# MCU_IO.net
KiCad netlist of a schematic drawn in Altium Designer
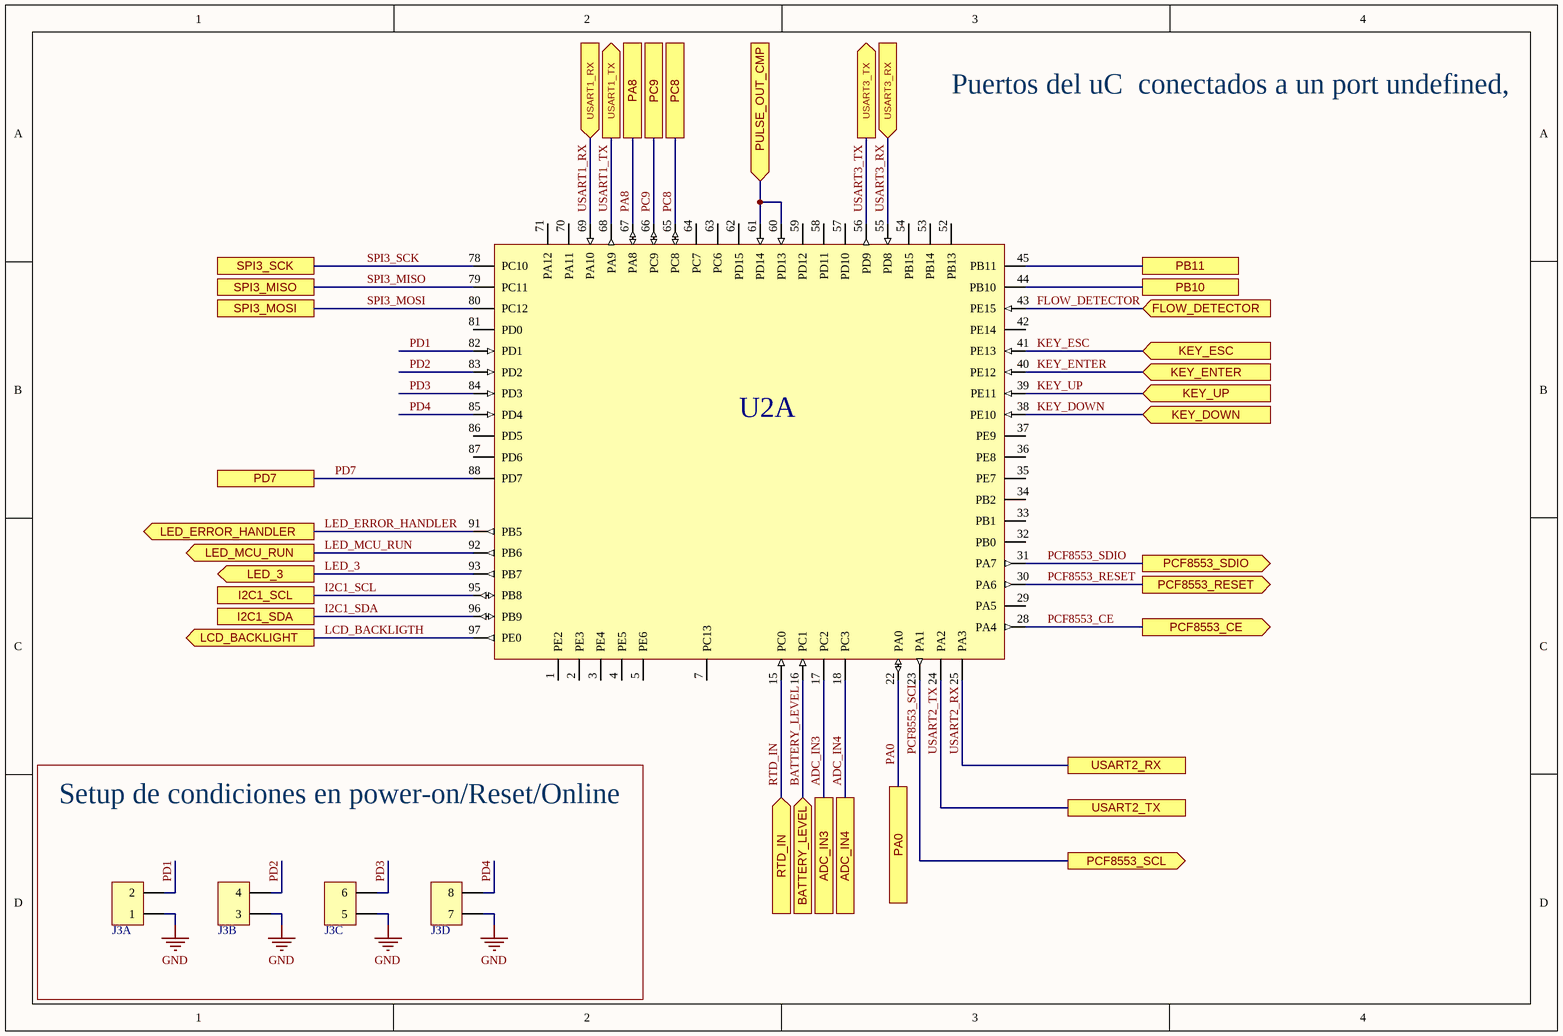
[diagram p0: MCU_IO.SchDoc]

(export (version "E")
  (design (tool "Eeschema 10.0.6"))
  (components
    (comp (ref "J3")
      (value "B-2100S08P-B110-JUMPER")
      (footprint "HEADER PIN 2X4")
      (description "2 x 4 - true hole  2.54mm")
      (fields
        (field (name "MANUFACTURER") "Ckmtw")
        (field (name "MANUFACTURER PART NUMBER") "B-2100S08P-B110")
      )
      (libsource (lib "header_pin") (part "B-2100S08P-B110-JUMPER"))
    )
    (comp (ref "U2")
      (value "STM32U575VI_1")
      (footprint "STM32U575VI")
      (fields (field (name "MANUFACTURER") "ST") (field (name "MANUFACTURER PART NUMBER") "STM32U575VIT6Q"))
      (libsource (lib "Microcontroladores") (part "STM32U575VI_1"))
    )
  )
  (nets
    (net (code "1") (name "/ADC_IN3") (class "Default")
      (node (ref "U2") (pin "17") (pinfunction "PC2_17") (pintype "tri_state"))
    )
    (net (code "2") (name "/ADC_IN4") (class "Default")
      (node (ref "U2") (pin "18") (pinfunction "PC3_18") (pintype "tri_state"))
    )
    (net (code "3") (name "/BATTERY_LEVEL") (class "Default")
      (node (ref "U2") (pin "16") (pinfunction "PC1_16") (pintype "input"))
    )
    (net (code "4") (name "/FLOW_DETECTOR") (class "Default")
      (node (ref "U2") (pin "43") (pinfunction "PE15_43") (pintype "input"))
    )
    (net (code "5") (name "/I2C1_SCL") (class "Default")
      (node (ref "U2") (pin "95") (pinfunction "PB8_95") (pintype "bidirectional"))
    )
    (net (code "6") (name "/I2C1_SDA") (class "Default")
      (node (ref "U2") (pin "96") (pinfunction "PB9_96") (pintype "bidirectional"))
    )
    (net (code "7") (name "/KEY_DOWN") (class "Default")
      (node (ref "U2") (pin "38") (pinfunction "PE10_38") (pintype "input"))
    )
    (net (code "8") (name "/KEY_ENTER") (class "Default")
      (node (ref "U2") (pin "40") (pinfunction "PE12_40") (pintype "input"))
    )
    (net (code "9") (name "/KEY_ESC") (class "Default")
      (node (ref "U2") (pin "41") (pinfunction "PE13_41") (pintype "input"))
    )
    (net (code "10") (name "/KEY_UP") (class "Default")
      (node (ref "U2") (pin "39") (pinfunction "PE11_39") (pintype "input"))
    )
    (net (code "11") (name "/LCD_BACKLIGTH") (class "Default")
      (node (ref "U2") (pin "97") (pinfunction "PE0_97") (pintype "output"))
    )
    (net (code "12") (name "/LED_3") (class "Default")
      (node (ref "U2") (pin "93") (pinfunction "PB7_93") (pintype "output"))
    )
    (net (code "13") (name "/LED_ERROR_HANDLER") (class "Default")
      (node (ref "U2") (pin "91") (pinfunction "PB5_91") (pintype "output"))
    )
    (net (code "14") (name "/LED_MCU_RUN") (class "Default")
      (node (ref "U2") (pin "92") (pinfunction "PB6_92") (pintype "output"))
    )
    (net (code "15") (name "/PA0") (class "Default")
      (node (ref "U2") (pin "22") (pinfunction "PA0_22") (pintype "bidirectional"))
    )
    (net (code "16") (name "/PA8") (class "Default")
      (node (ref "U2") (pin "67") (pinfunction "PA8_67") (pintype "bidirectional"))
    )
    (net (code "17") (name "/PB10") (class "Default")
      (node (ref "U2") (pin "44") (pinfunction "PB10_44") (pintype "tri_state"))
    )
    (net (code "18") (name "/PB11") (class "Default")
      (node (ref "U2") (pin "45") (pinfunction "PB11_45") (pintype "tri_state"))
    )
    (net (code "19") (name "/PC8") (class "Default")
      (node (ref "U2") (pin "65") (pinfunction "PC8_65") (pintype "bidirectional"))
    )
    (net (code "20") (name "/PC9") (class "Default")
      (node (ref "U2") (pin "66") (pinfunction "PC9_66") (pintype "bidirectional"))
    )
    (net (code "21") (name "/PCF8553_CE") (class "Default")
      (node (ref "U2") (pin "28") (pinfunction "PA4_28") (pintype "output"))
    )
    (net (code "22") (name "/PCF8553_RESET") (class "Default")
      (node (ref "U2") (pin "30") (pinfunction "PA6_30") (pintype "output"))
    )
    (net (code "23") (name "/PCF8553_SCL") (class "Default")
      (node (ref "U2") (pin "23") (pinfunction "PA1_23") (pintype "output"))
    )
    (net (code "24") (name "/PCF8553_SDIO") (class "Default")
      (node (ref "U2") (pin "31") (pinfunction "PA7_31") (pintype "output"))
    )
    (net (code "25") (name "/PD1") (class "Default")
      (node (ref "J3") (pin "2") (pinfunction "2_2") (pintype "passive"))
      (node (ref "U2") (pin "82") (pinfunction "PD1_82") (pintype "input"))
    )
    (net (code "26") (name "/PD2") (class "Default")
      (node (ref "J3") (pin "4") (pinfunction "4_4") (pintype "passive"))
      (node (ref "U2") (pin "83") (pinfunction "PD2_83") (pintype "input"))
    )
    (net (code "27") (name "/PD3") (class "Default")
      (node (ref "J3") (pin "6") (pinfunction "6_6") (pintype "passive"))
      (node (ref "U2") (pin "84") (pinfunction "PD3_84") (pintype "input"))
    )
    (net (code "28") (name "/PD4") (class "Default")
      (node (ref "J3") (pin "8") (pinfunction "8_8") (pintype "passive"))
      (node (ref "U2") (pin "85") (pinfunction "PD4_85") (pintype "input"))
    )
    (net (code "29") (name "/PD7") (class "Default")
      (node (ref "U2") (pin "88") (pinfunction "PD7_88") (pintype "passive"))
    )
    (net (code "30") (name "/PULSE_OUT_CMP") (class "Default")
      (node (ref "U2") (pin "60") (pinfunction "PD13_60") (pintype "input"))
      (node (ref "U2") (pin "61") (pinfunction "PD14_61") (pintype "input"))
    )
    (net (code "31") (name "/RTD_IN") (class "Default")
      (node (ref "U2") (pin "15") (pinfunction "PC0_15") (pintype "input"))
    )
    (net (code "32") (name "/SPI3_MISO") (class "Default")
      (node (ref "U2") (pin "79") (pinfunction "PC11_79") (pintype "tri_state"))
    )
    (net (code "33") (name "/SPI3_MOSI") (class "Default")
      (node (ref "U2") (pin "80") (pinfunction "PC12_80") (pintype "tri_state"))
    )
    (net (code "34") (name "/SPI3_SCK") (class "Default")
      (node (ref "U2") (pin "78") (pinfunction "PC10_78") (pintype "tri_state"))
    )
    (net (code "35") (name "/USART1_RX") (class "Default")
      (node (ref "U2") (pin "69") (pinfunction "PA10_69") (pintype "input"))
    )
    (net (code "36") (name "/USART1_TX") (class "Default")
      (node (ref "U2") (pin "68") (pinfunction "PA9_68") (pintype "output"))
    )
    (net (code "37") (name "/USART2_RX") (class "Default")
      (node (ref "U2") (pin "25") (pinfunction "PA3_25") (pintype "tri_state"))
    )
    (net (code "38") (name "/USART2_TX") (class "Default")
      (node (ref "U2") (pin "24") (pinfunction "PA2_24") (pintype "tri_state"))
    )
    (net (code "39") (name "/USART3_RX") (class "Default")
      (node (ref "U2") (pin "55") (pinfunction "PD8_55") (pintype "input"))
    )
    (net (code "40") (name "/USART3_TX") (class "Default")
      (node (ref "U2") (pin "56") (pinfunction "PD9_56") (pintype "output"))
    )
    (net (code "41") (name "GND") (class "Default")
      (node (ref "J3") (pin "1") (pinfunction "1_1") (pintype "passive"))
      (node (ref "J3") (pin "3") (pinfunction "3_3") (pintype "passive"))
      (node (ref "J3") (pin "5") (pinfunction "5_5") (pintype "passive"))
      (node (ref "J3") (pin "7") (pinfunction "7_7") (pintype "passive"))
    )
    (net (code "42") (name "unconnected-(U2A-PA5-Pad29)") (class "Default")
      (node (ref "U2") (pin "29") (pinfunction "PA5_29") (pintype "tri_state"))
    )
    (net (code "43") (name "unconnected-(U2A-PA11-Pad70)") (class "Default")
      (node (ref "U2") (pin "70") (pinfunction "PA11_70") (pintype "tri_state"))
    )
    (net (code "44") (name "unconnected-(U2A-PA12-Pad71)") (class "Default")
      (node (ref "U2") (pin "71") (pinfunction "PA12_71") (pintype "tri_state"))
    )
    (net (code "45") (name "unconnected-(U2A-PB0-Pad32)") (class "Default")
      (node (ref "U2") (pin "32") (pinfunction "PB0_32") (pintype "tri_state"))
    )
    (net (code "46") (name "unconnected-(U2A-PB1-Pad33)") (class "Default")
      (node (ref "U2") (pin "33") (pinfunction "PB1_33") (pintype "tri_state"))
    )
    (net (code "47") (name "unconnected-(U2A-PB2-Pad34)") (class "Default")
      (node (ref "U2") (pin "34") (pinfunction "PB2_34") (pintype "tri_state"))
    )
    (net (code "48") (name "unconnected-(U2A-PB13-Pad52)") (class "Default")
      (node (ref "U2") (pin "52") (pinfunction "PB13_52") (pintype "tri_state"))
    )
    (net (code "49") (name "unconnected-(U2A-PB14-Pad53)") (class "Default")
      (node (ref "U2") (pin "53") (pinfunction "PB14_53") (pintype "tri_state"))
    )
    (net (code "50") (name "unconnected-(U2A-PB15-Pad54)") (class "Default")
      (node (ref "U2") (pin "54") (pinfunction "PB15_54") (pintype "tri_state"))
    )
    (net (code "51") (name "unconnected-(U2A-PC6-Pad63)") (class "Default")
      (node (ref "U2") (pin "63") (pinfunction "PC6_63") (pintype "tri_state"))
    )
    (net (code "52") (name "unconnected-(U2A-PC7-Pad64)") (class "Default")
      (node (ref "U2") (pin "64") (pinfunction "PC7_64") (pintype "tri_state"))
    )
    (net (code "53") (name "unconnected-(U2A-PC13-Pad7)") (class "Default")
      (node (ref "U2") (pin "7") (pinfunction "PC13_7") (pintype "tri_state"))
    )
    (net (code "54") (name "unconnected-(U2A-PD0-Pad81)") (class "Default")
      (node (ref "U2") (pin "81") (pinfunction "PD0_81") (pintype "tri_state"))
    )
    (net (code "55") (name "unconnected-(U2A-PD5-Pad86)") (class "Default")
      (node (ref "U2") (pin "86") (pinfunction "PD5_86") (pintype "tri_state"))
    )
    (net (code "56") (name "unconnected-(U2A-PD6-Pad87)") (class "Default")
      (node (ref "U2") (pin "87") (pinfunction "PD6_87") (pintype "tri_state"))
    )
    (net (code "57") (name "unconnected-(U2A-PD10-Pad57)") (class "Default")
      (node (ref "U2") (pin "57") (pinfunction "PD10_57") (pintype "tri_state"))
    )
    (net (code "58") (name "unconnected-(U2A-PD11-Pad58)") (class "Default")
      (node (ref "U2") (pin "58") (pinfunction "PD11_58") (pintype "tri_state"))
    )
    (net (code "59") (name "unconnected-(U2A-PD12-Pad59)") (class "Default")
      (node (ref "U2") (pin "59") (pinfunction "PD12_59") (pintype "tri_state"))
    )
    (net (code "60") (name "unconnected-(U2A-PD15-Pad62)") (class "Default")
      (node (ref "U2") (pin "62") (pinfunction "PD15_62") (pintype "tri_state"))
    )
    (net (code "61") (name "unconnected-(U2A-PE2-Pad1)") (class "Default")
      (node (ref "U2") (pin "1") (pinfunction "PE2_1") (pintype "tri_state"))
    )
    (net (code "62") (name "unconnected-(U2A-PE3-Pad2)") (class "Default")
      (node (ref "U2") (pin "2") (pinfunction "PE3_2") (pintype "tri_state"))
    )
    (net (code "63") (name "unconnected-(U2A-PE4-Pad3)") (class "Default")
      (node (ref "U2") (pin "3") (pinfunction "PE4_3") (pintype "tri_state"))
    )
    (net (code "64") (name "unconnected-(U2A-PE5-Pad4)") (class "Default")
      (node (ref "U2") (pin "4") (pinfunction "PE5_4") (pintype "tri_state"))
    )
    (net (code "65") (name "unconnected-(U2A-PE6-Pad5)") (class "Default")
      (node (ref "U2") (pin "5") (pinfunction "PE6_5") (pintype "tri_state"))
    )
    (net (code "66") (name "unconnected-(U2A-PE7-Pad35)") (class "Default")
      (node (ref "U2") (pin "35") (pinfunction "PE7_35") (pintype "tri_state"))
    )
    (net (code "67") (name "unconnected-(U2A-PE8-Pad36)") (class "Default")
      (node (ref "U2") (pin "36") (pinfunction "PE8_36") (pintype "tri_state"))
    )
    (net (code "68") (name "unconnected-(U2A-PE9-Pad37)") (class "Default")
      (node (ref "U2") (pin "37") (pinfunction "PE9_37") (pintype "tri_state"))
    )
    (net (code "69") (name "unconnected-(U2A-PE14-Pad42)") (class "Default")
      (node (ref "U2") (pin "42") (pinfunction "PE14_42") (pintype "tri_state"))
    )
  )
)
